# Sheet1.net
KiCad netlist of a schematic drawn in Altium Designer
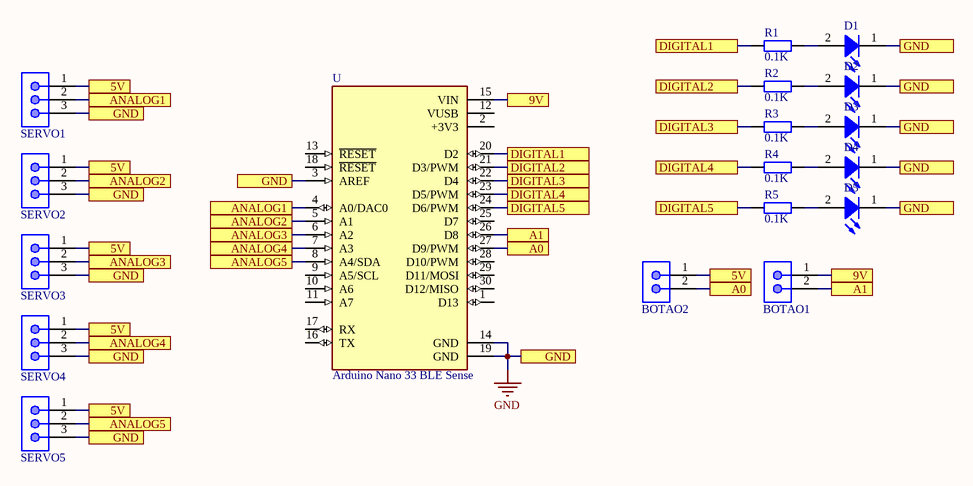
[diagram p0: Sheet1.SchDoc]

(export (version "E")
  (design (tool "Eeschema 10.0.6"))
  (components
    (comp (ref "BOTAO1")
      (value "61300211121")
      (footprint "61300211121")
      (description "WR-PHD Pin Header, THT, pitch 2.54mm, Single Row, Vertical, 2pin")
      (fields (field (name "PUBLISHER") "Wurth Elektronik"))
      (libsource (lib "Biblioteca_Ex_Machina_v1.6.0") (part "61300211121"))
    )
    (comp (ref "BOTAO2")
      (value "61300211121")
      (footprint "61300211121")
      (description "WR-PHD Pin Header, THT, pitch 2.54mm, Single Row, Vertical, 2pin")
      (fields (field (name "PUBLISHER") "Wurth Elektronik"))
      (libsource (lib "Biblioteca_Ex_Machina_v1.6.0") (part "61300211121"))
    )
    (comp (ref "D1")
      (value "Blue, 3.2V, 40deg")
      (footprint "LED GREEN 3MM")
      (description "LED WL-TMRC THT Mono-color Round")
      (fields (field (name "PART NUMBER") "151051BS04000") (field (name "PUBLISHER") "Wurth Elektronik"))
      (libsource (lib "Biblioteca_Ex_Machina_v1.6.0") (part "LED"))
    )
    (comp (ref "D2")
      (value "Blue, 3.2V, 40deg")
      (footprint "LED GREEN 3MM")
      (description "LED WL-TMRC THT Mono-color Round")
      (fields (field (name "PART NUMBER") "151051BS04000") (field (name "PUBLISHER") "Wurth Elektronik"))
      (libsource (lib "Biblioteca_Ex_Machina_v1.6.0") (part "LED"))
    )
    (comp (ref "D3")
      (value "Blue, 3.2V, 40deg")
      (footprint "LED GREEN 3MM")
      (description "LED WL-TMRC THT Mono-color Round")
      (fields (field (name "PART NUMBER") "151051BS04000") (field (name "PUBLISHER") "Wurth Elektronik"))
      (libsource (lib "Biblioteca_Ex_Machina_v1.6.0") (part "LED"))
    )
    (comp (ref "D4")
      (value "Blue, 3.2V, 40deg")
      (footprint "LED GREEN 3MM")
      (description "LED WL-TMRC THT Mono-color Round")
      (fields (field (name "PART NUMBER") "151051BS04000") (field (name "PUBLISHER") "Wurth Elektronik"))
      (libsource (lib "Biblioteca_Ex_Machina_v1.6.0") (part "LED"))
    )
    (comp (ref "D5")
      (value "Blue, 3.2V, 40deg")
      (footprint "LED GREEN 3MM")
      (description "LED WL-TMRC THT Mono-color Round")
      (fields (field (name "PART NUMBER") "151051BS04000") (field (name "PUBLISHER") "Wurth Elektronik"))
      (libsource (lib "Biblioteca_Ex_Machina_v1.6.0") (part "LED"))
    )
    (comp (ref "R1")
      (value "0.1K")
      (footprint "RES AXIAL-0.4")
      (description "Resistor")
      (fields (field (name "Comment") "Res") (field (name "PUBLISHER") "Altium Limited"))
      (libsource (lib "Biblioteca_Ex_Machina_v1.6.0") (part "Res"))
    )
    (comp (ref "R2")
      (value "0.1K")
      (footprint "RES AXIAL-0.4")
      (description "Resistor")
      (fields (field (name "Comment") "Res") (field (name "PUBLISHER") "Altium Limited"))
      (libsource (lib "Biblioteca_Ex_Machina_v1.6.0") (part "Res"))
    )
    (comp (ref "R3")
      (value "0.1K")
      (footprint "RES AXIAL-0.4")
      (description "Resistor")
      (fields (field (name "Comment") "Res") (field (name "PUBLISHER") "Altium Limited"))
      (libsource (lib "Biblioteca_Ex_Machina_v1.6.0") (part "Res"))
    )
    (comp (ref "R4")
      (value "0.1K")
      (footprint "RES AXIAL-0.4")
      (description "Resistor")
      (fields (field (name "Comment") "Res") (field (name "PUBLISHER") "Altium Limited"))
      (libsource (lib "Biblioteca_Ex_Machina_v1.6.0") (part "Res"))
    )
    (comp (ref "R5")
      (value "0.1K")
      (footprint "RES AXIAL-0.4")
      (description "Resistor")
      (fields (field (name "Comment") "Res") (field (name "PUBLISHER") "Altium Limited"))
      (libsource (lib "Biblioteca_Ex_Machina_v1.6.0") (part "Res"))
    )
    (comp (ref "SERVO1")
      (value "61300311121")
      (footprint "61300311121")
      (description "WR-PHD Pin Header, THT, pitch 2.54mm, Single Row, Vertical, 3pin")
      (fields (field (name "PUBLISHER") "Wurth Elektronik"))
      (libsource (lib "Biblioteca_Ex_Machina_v1.6.0") (part "61300311121"))
    )
    (comp (ref "SERVO2")
      (value "61300311121")
      (footprint "61300311121")
      (description "WR-PHD Pin Header, THT, pitch 2.54mm, Single Row, Vertical, 3pin")
      (fields (field (name "PUBLISHER") "Wurth Elektronik"))
      (libsource (lib "Biblioteca_Ex_Machina_v1.6.0") (part "61300311121"))
    )
    (comp (ref "SERVO3")
      (value "61300311121")
      (footprint "61300311121")
      (description "WR-PHD Pin Header, THT, pitch 2.54mm, Single Row, Vertical, 3pin")
      (fields (field (name "PUBLISHER") "Wurth Elektronik"))
      (libsource (lib "Biblioteca_Ex_Machina_v1.6.0") (part "61300311121"))
    )
    (comp (ref "SERVO4")
      (value "61300311121")
      (footprint "61300311121")
      (description "WR-PHD Pin Header, THT, pitch 2.54mm, Single Row, Vertical, 3pin")
      (fields (field (name "PUBLISHER") "Wurth Elektronik"))
      (libsource (lib "Biblioteca_Ex_Machina_v1.6.0") (part "61300311121"))
    )
    (comp (ref "SERVO5")
      (value "61300311121")
      (footprint "61300311121")
      (description "WR-PHD Pin Header, THT, pitch 2.54mm, Single Row, Vertical, 3pin")
      (fields (field (name "PUBLISHER") "Wurth Elektronik"))
      (libsource (lib "Biblioteca_Ex_Machina_v1.6.0") (part "61300311121"))
    )
    (comp (ref "U")
      (value "Arduino Nano 33 BLE Sense")
      (footprint "MODULE_ABX00027")
      (fields (field (name "MP") "ABX00027") (field (name "MF") "Arduino"))
      (libsource (lib "Biblioteca_Ex_Machina_v1.6.0") (part "Arduino Nano 33 BLE Sense"))
    )
  )
  (nets
    (net (code "1") (name "/5V") (class "Default")
      (node (ref "BOTAO2") (pin "1") (pinfunction "1_1") (pintype "passive"))
      (node (ref "SERVO1") (pin "1") (pinfunction "1_1") (pintype "passive"))
      (node (ref "SERVO2") (pin "1") (pinfunction "1_1") (pintype "passive"))
      (node (ref "SERVO3") (pin "1") (pinfunction "1_1") (pintype "passive"))
      (node (ref "SERVO4") (pin "1") (pinfunction "1_1") (pintype "passive"))
      (node (ref "SERVO5") (pin "1") (pinfunction "1_1") (pintype "passive"))
    )
    (net (code "2") (name "/9V") (class "Default")
      (node (ref "BOTAO1") (pin "1") (pinfunction "1_1") (pintype "passive"))
      (node (ref "U") (pin "15") (pinfunction "VIN_15") (pintype "power_in"))
    )
    (net (code "3") (name "/A0") (class "Default")
      (node (ref "BOTAO2") (pin "2") (pinfunction "2_2") (pintype "passive"))
      (node (ref "U") (pin "27") (pinfunction "D9/PWM_27") (pintype "bidirectional"))
    )
    (net (code "4") (name "/A1") (class "Default")
      (node (ref "BOTAO1") (pin "2") (pinfunction "2_2") (pintype "passive"))
      (node (ref "U") (pin "26") (pinfunction "D8_26") (pintype "bidirectional"))
    )
    (net (code "5") (name "/ANALOG1") (class "Default")
      (node (ref "SERVO1") (pin "2") (pinfunction "2_2") (pintype "passive"))
      (node (ref "U") (pin "4") (pinfunction "A0/DAC0_4") (pintype "bidirectional"))
    )
    (net (code "6") (name "/ANALOG2") (class "Default")
      (node (ref "SERVO2") (pin "2") (pinfunction "2_2") (pintype "passive"))
      (node (ref "U") (pin "5") (pinfunction "A1_5") (pintype "input"))
    )
    (net (code "7") (name "/ANALOG3") (class "Default")
      (node (ref "SERVO3") (pin "2") (pinfunction "2_2") (pintype "passive"))
      (node (ref "U") (pin "6") (pinfunction "A2_6") (pintype "input"))
    )
    (net (code "8") (name "/ANALOG4") (class "Default")
      (node (ref "SERVO4") (pin "2") (pinfunction "2_2") (pintype "passive"))
      (node (ref "U") (pin "7") (pinfunction "A3_7") (pintype "input"))
    )
    (net (code "9") (name "/ANALOG5") (class "Default")
      (node (ref "SERVO5") (pin "2") (pinfunction "2_2") (pintype "passive"))
      (node (ref "U") (pin "8") (pinfunction "A4/SDA_8") (pintype "input"))
    )
    (net (code "10") (name "/DIGITAL1") (class "Default")
      (node (ref "R1") (pin "1") (pinfunction "1_1") (pintype "passive"))
      (node (ref "U") (pin "20") (pinfunction "D2_20") (pintype "bidirectional"))
    )
    (net (code "11") (name "/DIGITAL2") (class "Default")
      (node (ref "R2") (pin "1") (pinfunction "1_1") (pintype "passive"))
      (node (ref "U") (pin "21") (pinfunction "D3/PWM_21") (pintype "bidirectional"))
    )
    (net (code "12") (name "/DIGITAL3") (class "Default")
      (node (ref "R3") (pin "1") (pinfunction "1_1") (pintype "passive"))
      (node (ref "U") (pin "22") (pinfunction "D4_22") (pintype "bidirectional"))
    )
    (net (code "13") (name "/DIGITAL4") (class "Default")
      (node (ref "R4") (pin "1") (pinfunction "1_1") (pintype "passive"))
      (node (ref "U") (pin "23") (pinfunction "D5/PWM_23") (pintype "bidirectional"))
    )
    (net (code "14") (name "/DIGITAL5") (class "Default")
      (node (ref "R5") (pin "1") (pinfunction "1_1") (pintype "passive"))
      (node (ref "U") (pin "24") (pinfunction "D6/PWM_24") (pintype "bidirectional"))
    )
    (net (code "15") (name "GND") (class "Default")
      (node (ref "D1") (pin "1") (pinfunction "K_1") (pintype "passive"))
      (node (ref "D2") (pin "1") (pinfunction "K_1") (pintype "passive"))
      (node (ref "D3") (pin "1") (pinfunction "K_1") (pintype "passive"))
      (node (ref "D4") (pin "1") (pinfunction "K_1") (pintype "passive"))
      (node (ref "D5") (pin "1") (pinfunction "K_1") (pintype "passive"))
      (node (ref "SERVO1") (pin "3") (pinfunction "3_3") (pintype "passive"))
      (node (ref "SERVO2") (pin "3") (pinfunction "3_3") (pintype "passive"))
      (node (ref "SERVO3") (pin "3") (pinfunction "3_3") (pintype "passive"))
      (node (ref "SERVO4") (pin "3") (pinfunction "3_3") (pintype "passive"))
      (node (ref "SERVO5") (pin "3") (pinfunction "3_3") (pintype "passive"))
      (node (ref "U") (pin "14") (pinfunction "GND_14") (pintype "power_in"))
      (node (ref "U") (pin "19") (pinfunction "GND_19") (pintype "power_in"))
      (node (ref "U") (pin "3") (pinfunction "AREF_3") (pintype "input"))
    )
    (net (code "16") (name "Net-(D1-A)") (class "Default")
      (node (ref "D1") (pin "2") (pinfunction "A_2") (pintype "passive"))
      (node (ref "R1") (pin "2") (pinfunction "2_2") (pintype "passive"))
    )
    (net (code "17") (name "Net-(D2-A)") (class "Default")
      (node (ref "D2") (pin "2") (pinfunction "A_2") (pintype "passive"))
      (node (ref "R2") (pin "2") (pinfunction "2_2") (pintype "passive"))
    )
    (net (code "18") (name "Net-(D3-A)") (class "Default")
      (node (ref "D3") (pin "2") (pinfunction "A_2") (pintype "passive"))
      (node (ref "R3") (pin "2") (pinfunction "2_2") (pintype "passive"))
    )
    (net (code "19") (name "Net-(D4-A)") (class "Default")
      (node (ref "D4") (pin "2") (pinfunction "A_2") (pintype "passive"))
      (node (ref "R4") (pin "2") (pinfunction "2_2") (pintype "passive"))
    )
    (net (code "20") (name "Net-(D5-A)") (class "Default")
      (node (ref "D5") (pin "2") (pinfunction "A_2") (pintype "passive"))
      (node (ref "R5") (pin "2") (pinfunction "2_2") (pintype "passive"))
    )
    (net (code "21") (name "unconnected-(U-+3V3-Pad2)") (class "Default")
      (node (ref "U") (pin "2") (pinfunction "+3V3_2") (pintype "power_in"))
    )
    (net (code "22") (name "unconnected-(U-A5{slash}SCL-Pad9)") (class "Default")
      (node (ref "U") (pin "9") (pinfunction "A5/SCL_9") (pintype "input"))
    )
    (net (code "23") (name "unconnected-(U-A6-Pad10)") (class "Default")
      (node (ref "U") (pin "10") (pinfunction "A6_10") (pintype "input"))
    )
    (net (code "24") (name "unconnected-(U-A7-Pad11)") (class "Default")
      (node (ref "U") (pin "11") (pinfunction "A7_11") (pintype "input"))
    )
    (net (code "25") (name "unconnected-(U-D7-Pad25)") (class "Default")
      (node (ref "U") (pin "25") (pinfunction "D7_25") (pintype "bidirectional"))
    )
    (net (code "26") (name "unconnected-(U-D10{slash}PWM-Pad28)") (class "Default")
      (node (ref "U") (pin "28") (pinfunction "D10/PWM_28") (pintype "bidirectional"))
    )
    (net (code "27") (name "unconnected-(U-D11{slash}MOSI-Pad29)") (class "Default")
      (node (ref "U") (pin "29") (pinfunction "D11/MOSI_29") (pintype "bidirectional"))
    )
    (net (code "28") (name "unconnected-(U-D12{slash}MISO-Pad30)") (class "Default")
      (node (ref "U") (pin "30") (pinfunction "D12/MISO_30") (pintype "bidirectional"))
    )
    (net (code "29") (name "unconnected-(U-D13-Pad1)") (class "Default")
      (node (ref "U") (pin "1") (pinfunction "D13_1") (pintype "bidirectional"))
    )
    (net (code "30") (name "unconnected-(U-RX-Pad17)") (class "Default")
      (node (ref "U") (pin "17") (pinfunction "RX_17") (pintype "bidirectional"))
    )
    (net (code "31") (name "unconnected-(U-TX-Pad16)") (class "Default")
      (node (ref "U") (pin "16") (pinfunction "TX_16") (pintype "bidirectional"))
    )
    (net (code "32") (name "unconnected-(U-VUSB-Pad12)") (class "Default")
      (node (ref "U") (pin "12") (pinfunction "VUSB_12") (pintype "power_in"))
    )
    (net (code "33") (name "unconnected-(U-~{RESET}-Pad13)") (class "Default")
      (node (ref "U") (pin "13") (pinfunction "~{RESET}_13") (pintype "input"))
    )
    (net (code "34") (name "unconnected-(U-~{RESET}-Pad18)") (class "Default")
      (node (ref "U") (pin "18") (pinfunction "~{RESET}_18") (pintype "input"))
    )
  )
)
